# 3_RK3399_PMU.net
KiCad netlist of a schematic drawn in Altium Designer
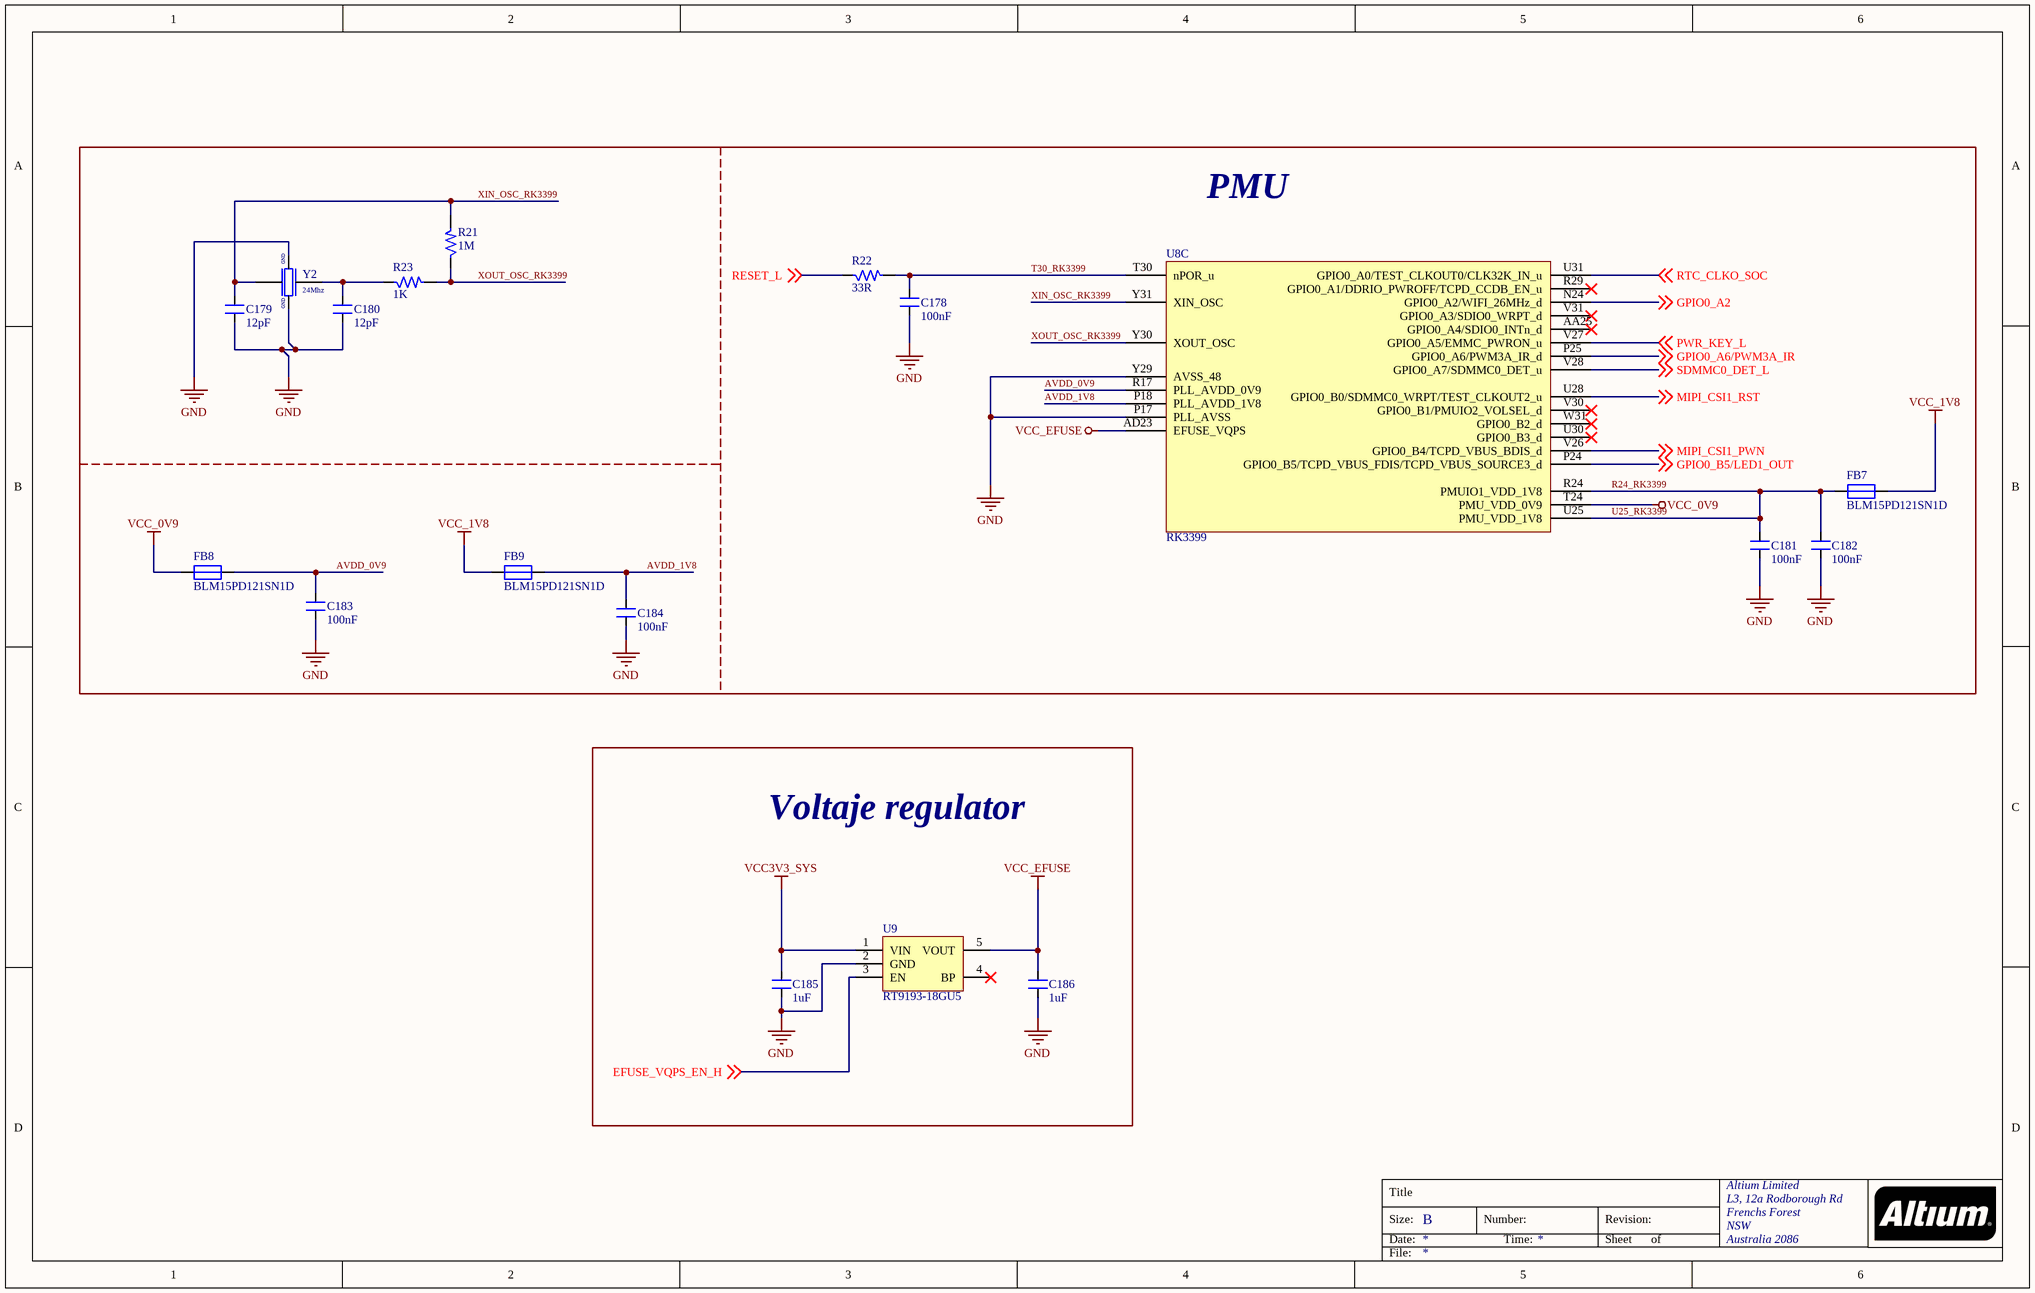
[diagram p0: [3] RK3399_PMU.SchDoc]

(export (version "E")
  (design (tool "Eeschema 10.0.6"))
  (components
    (comp (ref "C178")
      (value "100nF")
      (footprint "CAP_0201")
      (description "0.1µF ±10% 25V Ceramic Capacitor X5R 0201 (0603 Metric)")
      (fields
        (field (name "MANUFACTURER") "TDK Corporation")
        (field (name "MANUFACTURER PART NUMBER") "C0603X5R1E104K030BB")
      )
      (libsource (lib "EsteemPCB_SOM_Course_intlib") (part "CAP_100nF-25V-10%-0201"))
    )
    (comp (ref "C179")
      (value "12pF")
      (footprint "CAP_0201")
      (description "12pF ±10% 16V Ceramic Capacitor C0G, NP0 0201 (0603 Metric)")
      (fields
        (field (name "MANUFACTURER") "AVX Corporation")
        (field (name "MANUFACTURER PART NUMBER") "0201YA120KAT2A")
      )
      (libsource (lib "EsteemPCB_SOM_Course_intlib") (part "CAP_12pF-16V-10%-0201"))
    )
    (comp (ref "C180")
      (value "12pF")
      (footprint "CAP_0201")
      (description "12pF ±10% 16V Ceramic Capacitor C0G, NP0 0201 (0603 Metric)")
      (fields
        (field (name "MANUFACTURER") "AVX Corporation")
        (field (name "MANUFACTURER PART NUMBER") "0201YA120KAT2A")
      )
      (libsource (lib "EsteemPCB_SOM_Course_intlib") (part "CAP_12pF-16V-10%-0201"))
    )
    (comp (ref "C181")
      (value "100nF")
      (footprint "CAP_0201")
      (description "0.1µF ±10% 25V Ceramic Capacitor X5R 0201 (0603 Metric)")
      (fields
        (field (name "MANUFACTURER") "TDK Corporation")
        (field (name "MANUFACTURER PART NUMBER") "C0603X5R1E104K030BB")
      )
      (libsource (lib "EsteemPCB_SOM_Course_intlib") (part "CAP_100nF-25V-10%-0201"))
    )
    (comp (ref "C182")
      (value "100nF")
      (footprint "CAP_0201")
      (description "0.1µF ±10% 25V Ceramic Capacitor X5R 0201 (0603 Metric)")
      (fields
        (field (name "MANUFACTURER") "TDK Corporation")
        (field (name "MANUFACTURER PART NUMBER") "C0603X5R1E104K030BB")
      )
      (libsource (lib "EsteemPCB_SOM_Course_intlib") (part "CAP_100nF-25V-10%-0201"))
    )
    (comp (ref "C183")
      (value "100nF")
      (footprint "CAP_0201")
      (description "0.1µF ±10% 25V Ceramic Capacitor X5R 0201 (0603 Metric)")
      (fields
        (field (name "MANUFACTURER") "TDK Corporation")
        (field (name "MANUFACTURER PART NUMBER") "C0603X5R1E104K030BB")
      )
      (libsource (lib "EsteemPCB_SOM_Course_intlib") (part "CAP_100nF-25V-10%-0201"))
    )
    (comp (ref "C184")
      (value "100nF")
      (footprint "CAP_0201")
      (description "0.1µF ±10% 25V Ceramic Capacitor X5R 0201 (0603 Metric)")
      (fields
        (field (name "MANUFACTURER") "TDK Corporation")
        (field (name "MANUFACTURER PART NUMBER") "C0603X5R1E104K030BB")
      )
      (libsource (lib "EsteemPCB_SOM_Course_intlib") (part "CAP_100nF-25V-10%-0201"))
    )
    (comp (ref "C185")
      (value "1uF")
      (footprint "CAP_0201")
      (description "1µF ±20% 16V Ceramic Capacitor X5R 0201 (0603 Metric)")
      (fields
        (field (name "MANUFACTURER") "Samsung Electro-Mechanics")
        (field (name "MANUFACTURER PART NUMBER") "CL03A105MO3NRNH")
      )
      (libsource (lib "EsteemPCB_SOM_Course_intlib") (part "CAP_1uF-16V-10%-0201"))
    )
    (comp (ref "C186")
      (value "1uF")
      (footprint "CAP_0201")
      (description "1µF ±20% 16V Ceramic Capacitor X5R 0201 (0603 Metric)")
      (fields
        (field (name "MANUFACTURER") "Samsung Electro-Mechanics")
        (field (name "MANUFACTURER PART NUMBER") "CL03A105MO3NRNH")
      )
      (libsource (lib "EsteemPCB_SOM_Course_intlib") (part "CAP_1uF-16V-10%-0201"))
    )
    (comp (ref "FB7")
      (value "BLM15PD121SN1D")
      (footprint "RES_0402")
      (description "120 Ohms @ 100MHz 1 Power Line Ferrite Bead 0402 (1005 Metric) 1.3A 90mOhm")
      (fields (field (name "MANUFACTURER") "Murata Electronics"))
      (libsource (lib "EsteemPCB_SOM_Course_intlib") (part "FB_120R-1.3A-100Mhz-0402"))
    )
    (comp (ref "FB8")
      (value "BLM15PD121SN1D")
      (footprint "RES_0402")
      (description "120 Ohms @ 100MHz 1 Power Line Ferrite Bead 0402 (1005 Metric) 1.3A 90mOhm")
      (fields (field (name "MANUFACTURER") "Murata Electronics"))
      (libsource (lib "EsteemPCB_SOM_Course_intlib") (part "FB_120R-1.3A-100Mhz-0402"))
    )
    (comp (ref "FB9")
      (value "BLM15PD121SN1D")
      (footprint "RES_0402")
      (description "120 Ohms @ 100MHz 1 Power Line Ferrite Bead 0402 (1005 Metric) 1.3A 90mOhm")
      (fields (field (name "MANUFACTURER") "Murata Electronics"))
      (libsource (lib "EsteemPCB_SOM_Course_intlib") (part "FB_120R-1.3A-100Mhz-0402"))
    )
    (comp (ref "R21")
      (value "1M")
      (footprint "RES_0201")
      (description "1 MOhms ±1% 0.05W, 1/20W Chip Resistor 0201 (0603 Metric) Thick Film")
      (fields
        (field (name "MANUFACTURER") "Yageo")
        (field (name "MANUFACTURER PART NUMBER") "RC0201FR-071ML")
      )
      (libsource (lib "EsteemPCB_SOM_Course_intlib") (part "RES_1M-0.05W-1%-0201"))
    )
    (comp (ref "R22")
      (value "33R")
      (footprint "RES_0201")
      (description "33 Ohms ±1% 0.05W, 1/20W Chip Resistor 0201 (0603 Metric) Thick Film")
      (fields
        (field (name "MANUFACTURER") "Yageo")
        (field (name "MANUFACTURER PART NUMBER") "RC0201FR-0733RL")
      )
      (libsource (lib "EsteemPCB_SOM_Course_intlib") (part "RES_33R-0.05W-1%-0201"))
    )
    (comp (ref "R23")
      (value "1K")
      (footprint "RES_0201")
      (description "1 kOhms ±1% 0.05W, 1/20W Chip Resistor 0201 (0603 Metric) Thick Film")
      (fields
        (field (name "MANUFACTURER") "Yageo")
        (field (name "MANUFACTURER PART NUMBER") "RC0201FR-071KL")
      )
      (libsource (lib "EsteemPCB_SOM_Course_intlib") (part "RES_1K-0.05W-1%-0201"))
    )
    (comp (ref "U8")
      (value "RK3399")
      (footprint "FBGA828_23_826X826")
      (description "RK3399 is a low power, high performance processor for computing, personal mobile.")
      (fields (field (name "MANUFACTURER") "Rockchip"))
      (libsource (lib "EsteemPCB_SOM_Course_intlib") (part "IC_RK3399-FCBGA828"))
    )
    (comp (ref "U9")
      (value "RT9193-18GU5")
      (footprint "SC70-5")
      (description "Linear Voltage Regulator IC 1 Output 300mA SC-70-5")
      (fields (field (name "MANUFACTURER") "Richtek USA Inc."))
      (libsource (lib "EsteemPCB_SOM_Course_intlib") (part "REG_1.8V-300mA-5.5V-SC70-5"))
    )
    (comp (ref "Y2")
      (value "24Mhz")
      (footprint "XTAL_ABM8AIG-24.000MHZ-12-2Z-T3")
      (description "24MHz ±20ppm Crystal 12pF 50 Ohms 4-SMD, No Lead")
      (fields
        (field (name "MANUFACTURER") "Abracon LLC")
        (field (name "MANUFACTURER PART NUMBER") "ABM8AIG-24.000MHZ-12-2Z-T3")
      )
      (libsource (lib "EsteemPCB_SOM_Course_intlib") (part "XTAL_24Mhz-12pF-4-SMD"))
    )
  )
  (nets
    (net (code "1") (name "/AVDD_0V9") (class "Default")
      (node (ref "C183") (pin "2") (pinfunction "2_2") (pintype "passive"))
      (node (ref "FB8") (pin "2") (pinfunction "2_2") (pintype "passive"))
      (node (ref "U8") (pin "R17") (pinfunction "PLL_AVDD_0V9_R17") (pintype "passive"))
    )
    (net (code "2") (name "/AVDD_1V8") (class "Default")
      (node (ref "C184") (pin "2") (pinfunction "2_2") (pintype "passive"))
      (node (ref "FB9") (pin "2") (pinfunction "2_2") (pintype "passive"))
      (node (ref "U8") (pin "P18") (pinfunction "PLL_AVDD_1V8_P18") (pintype "passive"))
    )
    (net (code "3") (name "/R24_RK3399") (class "Default")
      (node (ref "C181") (pin "2") (pinfunction "2_2") (pintype "passive"))
      (node (ref "C182") (pin "2") (pinfunction "2_2") (pintype "passive"))
      (node (ref "FB7") (pin "1") (pinfunction "1_1") (pintype "passive"))
      (node (ref "U8") (pin "R24") (pinfunction "PMUIO1_VDD_1V8_R24") (pintype "passive"))
      (node (ref "U8") (pin "U25") (pinfunction "PMU_VDD_1V8_U25") (pintype "passive"))
    )
    (net (code "4") (name "/T30_RK3399") (class "Default")
      (node (ref "C178") (pin "2") (pinfunction "2_2") (pintype "passive"))
      (node (ref "R22") (pin "2") (pinfunction "2_2") (pintype "passive"))
      (node (ref "U8") (pin "T30") (pinfunction "nPOR_u_T30") (pintype "passive"))
    )
    (net (code "5") (name "/XIN_OSC_RK3399") (class "Default")
      (node (ref "C179") (pin "2") (pinfunction "2_2") (pintype "passive"))
      (node (ref "R21") (pin "2") (pinfunction "2_2") (pintype "passive"))
      (node (ref "U8") (pin "Y31") (pinfunction "XIN_OSC_Y31") (pintype "passive"))
      (node (ref "Y2") (pin "1") (pinfunction "1_1") (pintype "passive"))
    )
    (net (code "6") (name "/XOUT_OSC_RK3399") (class "Default")
      (node (ref "R21") (pin "1") (pinfunction "1_1") (pintype "passive"))
      (node (ref "R23") (pin "2") (pinfunction "2_2") (pintype "passive"))
      (node (ref "U8") (pin "Y30") (pinfunction "XOUT_OSC_Y30") (pintype "passive"))
    )
    (net (code "7") (name "EFUSE_VQPS_EN_H") (class "Default")
      (node (ref "U9") (pin "3") (pinfunction "EN_3") (pintype "passive"))
    )
    (net (code "8") (name "GND") (class "Default")
      (node (ref "C178") (pin "1") (pinfunction "1_1") (pintype "passive"))
      (node (ref "C179") (pin "1") (pinfunction "1_1") (pintype "passive"))
      (node (ref "C180") (pin "1") (pinfunction "1_1") (pintype "passive"))
      (node (ref "C181") (pin "1") (pinfunction "1_1") (pintype "passive"))
      (node (ref "C182") (pin "1") (pinfunction "1_1") (pintype "passive"))
      (node (ref "C183") (pin "1") (pinfunction "1_1") (pintype "passive"))
      (node (ref "C184") (pin "1") (pinfunction "1_1") (pintype "passive"))
      (node (ref "C185") (pin "1") (pinfunction "1_1") (pintype "passive"))
      (node (ref "C186") (pin "1") (pinfunction "1_1") (pintype "passive"))
      (node (ref "U8") (pin "P17") (pinfunction "PLL_AVSS_P17") (pintype "passive"))
      (node (ref "U8") (pin "Y29") (pinfunction "AVSS_48_Y29") (pintype "passive"))
      (node (ref "U9") (pin "2") (pinfunction "GND_2") (pintype "passive"))
      (node (ref "Y2") (pin "2") (pinfunction "2_2") (pintype "passive"))
      (node (ref "Y2") (pin "4") (pinfunction "4_4") (pintype "passive"))
    )
    (net (code "9") (name "GPIO0_A2") (class "Default")
      (node (ref "U8") (pin "N24") (pinfunction "GPIO0_A2/WIFI_26MHz_d_N24") (pintype "passive"))
    )
    (net (code "10") (name "GPIO0_A6{slash}PWM3A_IR") (class "Default")
      (node (ref "U8") (pin "P25") (pinfunction "GPIO0_A6/PWM3A_IR_d_P25") (pintype "passive"))
    )
    (net (code "11") (name "GPIO0_B5{slash}LED1_OUT") (class "Default")
      (node (ref "U8") (pin "P24") (pinfunction "GPIO0_B5/TCPD_VBUS_FDIS/TCPD_VBUS_SOURCE3_d_P24") (pintype "passive"))
    )
    (net (code "12") (name "MIPI_CSI1_PWN") (class "Default")
      (node (ref "U8") (pin "V26") (pinfunction "GPIO0_B4/TCPD_VBUS_BDIS_d_V26") (pintype "passive"))
    )
    (net (code "13") (name "MIPI_CSI1_RST") (class "Default")
      (node (ref "U8") (pin "U28") (pinfunction "GPIO0_B0/SDMMC0_WRPT/TEST_CLKOUT2_u_U28") (pintype "passive"))
    )
    (net (code "14") (name "Net-(C180-Pad2)") (class "Default")
      (node (ref "C180") (pin "2") (pinfunction "2_2") (pintype "passive"))
      (node (ref "R23") (pin "1") (pinfunction "1_1") (pintype "passive"))
      (node (ref "Y2") (pin "3") (pinfunction "3_3") (pintype "passive"))
    )
    (net (code "15") (name "PWR_KEY_L") (class "Default")
      (node (ref "U8") (pin "V27") (pinfunction "GPIO0_A5/EMMC_PWRON_u_V27") (pintype "passive"))
    )
    (net (code "16") (name "RESET_L") (class "Default")
      (node (ref "R22") (pin "1") (pinfunction "1_1") (pintype "passive"))
    )
    (net (code "17") (name "RTC_CLKO_SOC") (class "Default")
      (node (ref "U8") (pin "U31") (pinfunction "GPIO0_A0/TEST_CLKOUT0/CLK32K_IN_u_U31") (pintype "passive"))
    )
    (net (code "18") (name "SDMMC0_DET_L") (class "Default")
      (node (ref "U8") (pin "V28") (pinfunction "GPIO0_A7/SDMMC0_DET_u_V28") (pintype "passive"))
    )
    (net (code "19") (name "VCC3V3_SYS") (class "Default")
      (node (ref "C185") (pin "2") (pinfunction "2_2") (pintype "passive"))
      (node (ref "U9") (pin "1") (pinfunction "VIN_1") (pintype "passive"))
    )
    (net (code "20") (name "VCC_0V9") (class "Default")
      (node (ref "FB8") (pin "1") (pinfunction "1_1") (pintype "passive"))
      (node (ref "U8") (pin "T24") (pinfunction "PMU_VDD_0V9_T24") (pintype "passive"))
    )
    (net (code "21") (name "VCC_1V8") (class "Default")
      (node (ref "FB7") (pin "2") (pinfunction "2_2") (pintype "passive"))
      (node (ref "FB9") (pin "1") (pinfunction "1_1") (pintype "passive"))
    )
    (net (code "22") (name "VCC_EFUSE") (class "Default")
      (node (ref "C186") (pin "2") (pinfunction "2_2") (pintype "passive"))
      (node (ref "U8") (pin "AD23") (pinfunction "EFUSE_VQPS_AD23") (pintype "passive"))
      (node (ref "U9") (pin "5") (pinfunction "VOUT_5") (pintype "passive"))
    )
    (net (code "23") (name "unconnected-(U8C-GPIO0_A1{slash}DDRIO_PWROFF{slash}TCPD_CCDB_EN_u-PadR29)") (class "Default")
      (node (ref "U8") (pin "R29") (pinfunction "GPIO0_A1/DDRIO_PWROFF/TCPD_CCDB_EN_u_R29") (pintype "passive+no_connect"))
    )
    (net (code "24") (name "unconnected-(U8C-GPIO0_A3{slash}SDIO0_WRPT_d-PadV31)") (class "Default")
      (node (ref "U8") (pin "V31") (pinfunction "GPIO0_A3/SDIO0_WRPT_d_V31") (pintype "passive+no_connect"))
    )
    (net (code "25") (name "unconnected-(U8C-GPIO0_A4{slash}SDIO0_INTn_d-PadAA25)") (class "Default")
      (node (ref "U8") (pin "AA25") (pinfunction "GPIO0_A4/SDIO0_INTn_d_AA25") (pintype "passive+no_connect"))
    )
    (net (code "26") (name "unconnected-(U8C-GPIO0_B1{slash}PMUIO2_VOLSEL_d-PadV30)") (class "Default")
      (node (ref "U8") (pin "V30") (pinfunction "GPIO0_B1/PMUIO2_VOLSEL_d_V30") (pintype "passive+no_connect"))
    )
    (net (code "27") (name "unconnected-(U8C-GPIO0_B2_d-PadW31)") (class "Default")
      (node (ref "U8") (pin "W31") (pinfunction "GPIO0_B2_d_W31") (pintype "passive+no_connect"))
    )
    (net (code "28") (name "unconnected-(U8C-GPIO0_B3_d-PadU30)") (class "Default")
      (node (ref "U8") (pin "U30") (pinfunction "GPIO0_B3_d_U30") (pintype "passive+no_connect"))
    )
    (net (code "29") (name "unconnected-(U9-BP-Pad4)") (class "Default")
      (node (ref "U9") (pin "4") (pinfunction "BP_4") (pintype "passive+no_connect"))
    )
  )
)
